# four-step-octaved_1_1.net
KiCad netlist of a schematic drawn in EAGLE
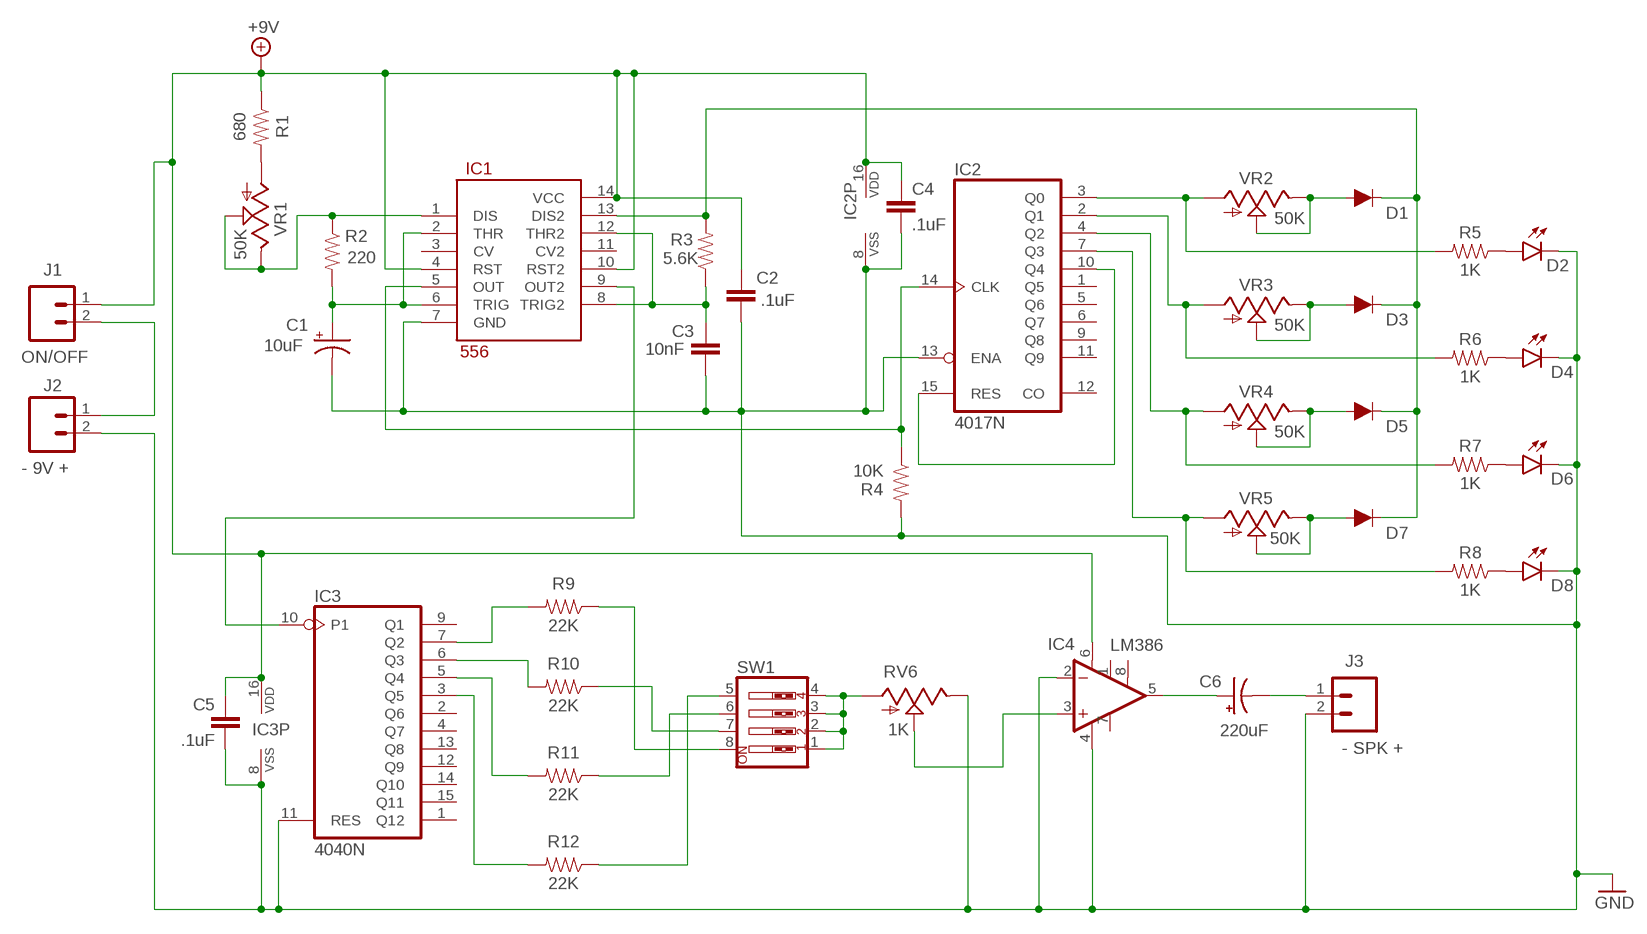
[diagram p0: schematic, sheet 1]

(export (version "E")
  (design (tool "Eeschema 10.0.6"))
  (components
    (comp (ref "C1")
      (value "10uF")
      (footprint "eagle-import:CPOL-RADIAL-2.5MM-5MM")
      (libsource (lib "eagle-import") (part "10UF-POLAR-RADIAL-2.5MM-25V-20%"))
    )
    (comp (ref "C2")
      (value ".1uF")
      (footprint "eagle-import:CAP-PTH-SMALL-KIT")
      (libsource (lib "eagle-import") (part "0.1UF-KIT-EZ-50V-20%"))
    )
    (comp (ref "C3")
      (value "10nF")
      (footprint "eagle-import:CAP-PTH-SMALL-KIT")
      (libsource (lib "eagle-import") (part "0.1UF-KIT-EZ-50V-20%"))
    )
    (comp (ref "C4")
      (value ".1uF")
      (footprint "eagle-import:CAP-PTH-SMALL-KIT")
      (libsource (lib "eagle-import") (part "0.1UF-KIT-EZ-50V-20%"))
    )
    (comp (ref "C5")
      (value ".1uF")
      (footprint "eagle-import:CAP-PTH-SMALL-KIT")
      (libsource (lib "eagle-import") (part "0.1UF-KIT-EZ-50V-20%"))
    )
    (comp (ref "C6")
      (value "220uF")
      (footprint "eagle-import:CPOL-RADIAL-2.5MM-5MM")
      (libsource (lib "eagle-import") (part "10UF-POLAR-RADIAL-2.5MM-25V-20%"))
    )
    (comp (ref "D1")
      (value "DIODE-PTH")
      (footprint "eagle-import:DIODE-1N4001")
      (libsource (lib "eagle-import") (part "DIODE-PTH"))
    )
    (comp (ref "D2")
      (value "LED3MM")
      (footprint "eagle-import:LED_3MM")
      (libsource (lib "eagle-import") (part "LED3MM"))
    )
    (comp (ref "D3")
      (value "DIODE-PTH")
      (footprint "eagle-import:DIODE-1N4001")
      (libsource (lib "eagle-import") (part "DIODE-PTH"))
    )
    (comp (ref "D4")
      (value "LED3MM")
      (footprint "eagle-import:LED_3MM")
      (libsource (lib "eagle-import") (part "LED3MM"))
    )
    (comp (ref "D5")
      (value "DIODE-PTH")
      (footprint "eagle-import:DIODE-1N4001")
      (libsource (lib "eagle-import") (part "DIODE-PTH"))
    )
    (comp (ref "D6")
      (value "LED3MM")
      (footprint "eagle-import:LED_3MM")
      (libsource (lib "eagle-import") (part "LED3MM"))
    )
    (comp (ref "D7")
      (value "DIODE-PTH")
      (footprint "eagle-import:DIODE-1N4001")
      (libsource (lib "eagle-import") (part "DIODE-PTH"))
    )
    (comp (ref "D8")
      (value "LED3MM")
      (footprint "eagle-import:LED_3MM")
      (libsource (lib "eagle-import") (part "LED3MM"))
    )
    (comp (ref "IC1")
      (value "556")
      (footprint "eagle-import:DIP14")
      (libsource (lib "eagle-import") (part "556"))
    )
    (comp (ref "IC2")
      (value "4017N")
      (footprint "eagle-import:DIL16")
      (libsource (lib "eagle-import") (part "4017N"))
    )
    (comp (ref "IC3")
      (value "4040N")
      (footprint "eagle-import:DIL16")
      (libsource (lib "eagle-import") (part "4040N"))
    )
    (comp (ref "IC4")
      (value "LM386")
      (footprint "eagle-import:DIP08")
      (libsource (lib "eagle-import") (part "LM386"))
    )
    (comp (ref "J1")
      (value "ON/OFF")
      (footprint "eagle-import:1X02")
      (libsource (lib "eagle-import") (part "CONN_02"))
    )
    (comp (ref "J2")
      (value "- 9V +")
      (footprint "eagle-import:1X02")
      (libsource (lib "eagle-import") (part "CONN_02"))
    )
    (comp (ref "J3")
      (value "- SPK +")
      (footprint "eagle-import:1X02")
      (libsource (lib "eagle-import") (part "CONN_02"))
    )
    (comp (ref "R1")
      (value "680")
      (footprint "eagle-import:AXIAL-0.3")
      (libsource (lib "eagle-import") (part "1KOHM-HORIZ-1/4W-1%"))
    )
    (comp (ref "R2")
      (value "220")
      (footprint "eagle-import:AXIAL-0.3")
      (libsource (lib "eagle-import") (part "1KOHM-HORIZ-1/4W-1%"))
    )
    (comp (ref "R3")
      (value "5.6K")
      (footprint "eagle-import:AXIAL-0.3")
      (libsource (lib "eagle-import") (part "1KOHM-HORIZ-1/4W-1%"))
    )
    (comp (ref "R4")
      (value "10K")
      (footprint "eagle-import:AXIAL-0.3")
      (libsource (lib "eagle-import") (part "1KOHM-HORIZ-1/4W-1%"))
    )
    (comp (ref "R5")
      (value "1K")
      (footprint "eagle-import:AXIAL-0.3")
      (libsource (lib "eagle-import") (part "1KOHM-HORIZ-1/4W-1%"))
    )
    (comp (ref "R6")
      (value "1K")
      (footprint "eagle-import:AXIAL-0.3")
      (libsource (lib "eagle-import") (part "1KOHM-HORIZ-1/4W-1%"))
    )
    (comp (ref "R7")
      (value "1K")
      (footprint "eagle-import:AXIAL-0.3")
      (libsource (lib "eagle-import") (part "1KOHM-HORIZ-1/4W-1%"))
    )
    (comp (ref "R8")
      (value "1K")
      (footprint "eagle-import:AXIAL-0.3")
      (libsource (lib "eagle-import") (part "1KOHM-HORIZ-1/4W-1%"))
    )
    (comp (ref "R9")
      (value "22K")
      (footprint "eagle-import:AXIAL-0.3")
      (libsource (lib "eagle-import") (part "1KOHM-HORIZ-1/4W-1%"))
    )
    (comp (ref "R10")
      (value "22K")
      (footprint "eagle-import:AXIAL-0.3")
      (libsource (lib "eagle-import") (part "1KOHM-HORIZ-1/4W-1%"))
    )
    (comp (ref "R11")
      (value "22K")
      (footprint "eagle-import:AXIAL-0.3")
      (libsource (lib "eagle-import") (part "1KOHM-HORIZ-1/4W-1%"))
    )
    (comp (ref "R12")
      (value "22K")
      (footprint "eagle-import:AXIAL-0.3")
      (libsource (lib "eagle-import") (part "1KOHM-HORIZ-1/4W-1%"))
    )
    (comp (ref "RV6")
      (value "1K")
      (footprint "eagle-import:TRIM_POT")
      (libsource (lib "eagle-import") (part "POTTRIM"))
    )
    (comp (ref "SW1")
      (value "SW_DIP-4")
      (footprint "eagle-import:EDG-04")
      (libsource (lib "eagle-import") (part "SW_DIP-4"))
    )
    (comp (ref "VR1")
      (value "50K")
      (footprint "eagle-import:TRIM_POT")
      (libsource (lib "eagle-import") (part "POTTRIM"))
    )
    (comp (ref "VR2")
      (value "50K")
      (footprint "eagle-import:TRIM_POT")
      (libsource (lib "eagle-import") (part "POTTRIM"))
    )
    (comp (ref "VR3")
      (value "50K")
      (footprint "eagle-import:TRIM_POT")
      (libsource (lib "eagle-import") (part "POTTRIM"))
    )
    (comp (ref "VR4")
      (value "50K")
      (footprint "eagle-import:TRIM_POT")
      (libsource (lib "eagle-import") (part "POTTRIM"))
    )
    (comp (ref "VR5")
      (value "50K")
      (footprint "eagle-import:TRIM_POT")
      (libsource (lib "eagle-import") (part "POTTRIM"))
    )
  )
  (nets
    (net (code "1") (name "+9V") (class "Default")
      (node (ref "C2") (pin "1") (pinfunction "1_1") (pintype "passive"))
      (node (ref "C4") (pin "1") (pinfunction "1_1") (pintype "passive"))
      (node (ref "C5") (pin "1") (pinfunction "1_1") (pintype "passive"))
      (node (ref "IC1") (pin "10") (pinfunction "RST2_10") (pintype "bidirectional"))
      (node (ref "IC1") (pin "14") (pinfunction "VCC_14") (pintype "bidirectional"))
      (node (ref "IC1") (pin "4") (pinfunction "RST_4") (pintype "bidirectional"))
      (node (ref "IC2") (pin "16") (pinfunction "VDD_16") (pintype "power_in"))
      (node (ref "IC3") (pin "16") (pinfunction "VDD_16") (pintype "power_in"))
      (node (ref "IC4") (pin "6") (pinfunction "V+_6") (pintype "power_in"))
      (node (ref "J1") (pin "1") (pinfunction "1_1") (pintype "passive"))
      (node (ref "R1") (pin "P$1") (pinfunction "1_P$1") (pintype "passive"))
    )
    (net (code "2") (name "GND") (class "Default")
      (node (ref "C1") (pin "2") (pinfunction "-_2") (pintype "passive"))
      (node (ref "C2") (pin "2") (pinfunction "2_2") (pintype "passive"))
      (node (ref "C3") (pin "2") (pinfunction "2_2") (pintype "passive"))
      (node (ref "C4") (pin "2") (pinfunction "2_2") (pintype "passive"))
      (node (ref "C5") (pin "2") (pinfunction "2_2") (pintype "passive"))
      (node (ref "D2") (pin "K") (pinfunction "C_K") (pintype "passive"))
      (node (ref "D4") (pin "K") (pinfunction "C_K") (pintype "passive"))
      (node (ref "D6") (pin "K") (pinfunction "C_K") (pintype "passive"))
      (node (ref "D8") (pin "K") (pinfunction "C_K") (pintype "passive"))
      (node (ref "IC1") (pin "7") (pinfunction "GND_7") (pintype "bidirectional"))
      (node (ref "IC2") (pin "13") (pinfunction "ENA_13") (pintype "input"))
      (node (ref "IC2") (pin "8") (pinfunction "VSS_8") (pintype "power_in"))
      (node (ref "IC3") (pin "11") (pinfunction "RES_11") (pintype "input"))
      (node (ref "IC3") (pin "8") (pinfunction "VSS_8") (pintype "power_in"))
      (node (ref "IC4") (pin "2") (pinfunction "-IN_2") (pintype "input"))
      (node (ref "IC4") (pin "4") (pinfunction "V-_4") (pintype "power_in"))
      (node (ref "J2") (pin "2") (pinfunction "2_2") (pintype "passive"))
      (node (ref "J3") (pin "2") (pinfunction "2_2") (pintype "passive"))
      (node (ref "R4") (pin "P$2") (pinfunction "2_P$2") (pintype "passive"))
      (node (ref "RV6") (pin "2") (pinfunction "E_2") (pintype "passive"))
    )
    (net (code "3") (name "Net-(C1-+)") (class "Default")
      (node (ref "C1") (pin "1") (pinfunction "+_1") (pintype "passive"))
      (node (ref "IC1") (pin "2") (pinfunction "THR_2") (pintype "bidirectional"))
      (node (ref "IC1") (pin "6") (pinfunction "TRIG_6") (pintype "bidirectional"))
      (node (ref "R2") (pin "P$2") (pinfunction "2_P$2") (pintype "passive"))
    )
    (net (code "4") (name "Net-(C6-+)") (class "Default")
      (node (ref "C6") (pin "1") (pinfunction "+_1") (pintype "passive"))
      (node (ref "IC4") (pin "5") (pinfunction "OUT_5") (pintype "output"))
    )
    (net (code "5") (name "Net-(C6--)") (class "Default")
      (node (ref "C6") (pin "2") (pinfunction "-_2") (pintype "passive"))
      (node (ref "J3") (pin "1") (pinfunction "1_1") (pintype "passive"))
    )
    (net (code "6") (name "Net-(IC1-DIS)") (class "Default")
      (node (ref "IC1") (pin "1") (pinfunction "DIS_1") (pintype "bidirectional"))
      (node (ref "R2") (pin "P$1") (pinfunction "1_P$1") (pintype "passive"))
      (node (ref "VR1") (pin "1") (pinfunction "S_1") (pintype "passive"))
      (node (ref "VR1") (pin "2") (pinfunction "E_2") (pintype "passive"))
    )
    (net (code "7") (name "Net-(IC1-DIS2)") (class "Default")
      (node (ref "D1") (pin "C") (pinfunction "C_C") (pintype "passive"))
      (node (ref "D3") (pin "C") (pinfunction "C_C") (pintype "passive"))
      (node (ref "D5") (pin "C") (pinfunction "C_C") (pintype "passive"))
      (node (ref "D7") (pin "C") (pinfunction "C_C") (pintype "passive"))
      (node (ref "IC1") (pin "13") (pinfunction "DIS2_13") (pintype "bidirectional"))
      (node (ref "R3") (pin "P$2") (pinfunction "2_P$2") (pintype "passive"))
    )
    (net (code "8") (name "Net-(IC1-OUT)") (class "Default")
      (node (ref "IC1") (pin "5") (pinfunction "OUT_5") (pintype "bidirectional"))
      (node (ref "IC2") (pin "14") (pinfunction "CLK_14") (pintype "input"))
      (node (ref "R4") (pin "P$1") (pinfunction "1_P$1") (pintype "passive"))
    )
    (net (code "9") (name "Net-(IC1-OUT2)") (class "Default")
      (node (ref "IC1") (pin "9") (pinfunction "OUT2_9") (pintype "bidirectional"))
      (node (ref "IC3") (pin "10") (pinfunction "P1_10") (pintype "input"))
    )
    (net (code "10") (name "Net-(IC1-THR2)") (class "Default")
      (node (ref "C3") (pin "1") (pinfunction "1_1") (pintype "passive"))
      (node (ref "IC1") (pin "12") (pinfunction "THR2_12") (pintype "bidirectional"))
      (node (ref "IC1") (pin "8") (pinfunction "TRIG2_8") (pintype "bidirectional"))
      (node (ref "R3") (pin "P$1") (pinfunction "1_P$1") (pintype "passive"))
    )
    (net (code "11") (name "Net-(IC2A-Q0)") (class "Default")
      (node (ref "IC2") (pin "3") (pinfunction "Q0_3") (pintype "output"))
      (node (ref "R5") (pin "P$2") (pinfunction "2_P$2") (pintype "passive"))
      (node (ref "VR2") (pin "3") (pinfunction "A_3") (pintype "passive"))
    )
    (net (code "12") (name "Net-(IC2A-Q1)") (class "Default")
      (node (ref "IC2") (pin "2") (pinfunction "Q1_2") (pintype "output"))
      (node (ref "R6") (pin "P$2") (pinfunction "2_P$2") (pintype "passive"))
      (node (ref "VR3") (pin "3") (pinfunction "A_3") (pintype "passive"))
    )
    (net (code "13") (name "Net-(IC2A-Q2)") (class "Default")
      (node (ref "IC2") (pin "4") (pinfunction "Q2_4") (pintype "output"))
      (node (ref "R7") (pin "P$2") (pinfunction "2_P$2") (pintype "passive"))
      (node (ref "VR4") (pin "3") (pinfunction "A_3") (pintype "passive"))
    )
    (net (code "14") (name "Net-(IC2A-Q3)") (class "Default")
      (node (ref "IC2") (pin "7") (pinfunction "Q3_7") (pintype "output"))
      (node (ref "R8") (pin "P$2") (pinfunction "2_P$2") (pintype "passive"))
      (node (ref "VR5") (pin "3") (pinfunction "A_3") (pintype "passive"))
    )
    (net (code "15") (name "Net-(IC2A-Q4)") (class "Default")
      (node (ref "IC2") (pin "10") (pinfunction "Q4_10") (pintype "output"))
      (node (ref "IC2") (pin "15") (pinfunction "RES_15") (pintype "input"))
    )
    (net (code "16") (name "Net-(IC3A-Q2)") (class "Default")
      (node (ref "IC3") (pin "7") (pinfunction "Q2_7") (pintype "output"))
      (node (ref "R9") (pin "P$2") (pinfunction "2_P$2") (pintype "passive"))
    )
    (net (code "17") (name "Net-(IC3A-Q3)") (class "Default")
      (node (ref "IC3") (pin "6") (pinfunction "Q3_6") (pintype "output"))
      (node (ref "R10") (pin "P$2") (pinfunction "2_P$2") (pintype "passive"))
    )
    (net (code "18") (name "Net-(IC3A-Q4)") (class "Default")
      (node (ref "IC3") (pin "5") (pinfunction "Q4_5") (pintype "output"))
      (node (ref "R11") (pin "P$2") (pinfunction "2_P$2") (pintype "passive"))
    )
    (net (code "19") (name "Net-(IC3A-Q5)") (class "Default")
      (node (ref "IC3") (pin "3") (pinfunction "Q5_3") (pintype "output"))
      (node (ref "R12") (pin "P$2") (pinfunction "2_P$2") (pintype "passive"))
    )
    (net (code "20") (name "Net-(IC4-+IN)") (class "Default")
      (node (ref "IC4") (pin "3") (pinfunction "+IN_3") (pintype "input"))
      (node (ref "RV6") (pin "1") (pinfunction "S_1") (pintype "passive"))
    )
    (net (code "21") (name "Net-(J1-Pad2)") (class "Default")
      (node (ref "J1") (pin "2") (pinfunction "2_2") (pintype "passive"))
      (node (ref "J2") (pin "1") (pinfunction "1_1") (pintype "passive"))
    )
    (net (code "22") (name "Net-(R1-2)") (class "Default")
      (node (ref "R1") (pin "P$2") (pinfunction "2_P$2") (pintype "passive"))
      (node (ref "VR1") (pin "3") (pinfunction "A_3") (pintype "passive"))
    )
    (net (code "23") (name "Net-(R5-1)") (class "Default")
      (node (ref "D2") (pin "A") (pinfunction "A_A") (pintype "passive"))
      (node (ref "R5") (pin "P$1") (pinfunction "1_P$1") (pintype "passive"))
    )
    (net (code "24") (name "Net-(R6-1)") (class "Default")
      (node (ref "D4") (pin "A") (pinfunction "A_A") (pintype "passive"))
      (node (ref "R6") (pin "P$1") (pinfunction "1_P$1") (pintype "passive"))
    )
    (net (code "25") (name "Net-(R7-1)") (class "Default")
      (node (ref "D6") (pin "A") (pinfunction "A_A") (pintype "passive"))
      (node (ref "R7") (pin "P$1") (pinfunction "1_P$1") (pintype "passive"))
    )
    (net (code "26") (name "Net-(R8-1)") (class "Default")
      (node (ref "D8") (pin "A") (pinfunction "A_A") (pintype "passive"))
      (node (ref "R8") (pin "P$1") (pinfunction "1_P$1") (pintype "passive"))
    )
    (net (code "27") (name "Net-(R9-1)") (class "Default")
      (node (ref "R9") (pin "P$1") (pinfunction "1_P$1") (pintype "passive"))
      (node (ref "SW1") (pin "8") (pinfunction "8_8") (pintype "passive"))
    )
    (net (code "28") (name "Net-(R10-1)") (class "Default")
      (node (ref "R10") (pin "P$1") (pinfunction "1_P$1") (pintype "passive"))
      (node (ref "SW1") (pin "7") (pinfunction "7_7") (pintype "passive"))
    )
    (net (code "29") (name "Net-(R11-1)") (class "Default")
      (node (ref "R11") (pin "P$1") (pinfunction "1_P$1") (pintype "passive"))
      (node (ref "SW1") (pin "6") (pinfunction "6_6") (pintype "passive"))
    )
    (net (code "30") (name "Net-(R12-1)") (class "Default")
      (node (ref "R12") (pin "P$1") (pinfunction "1_P$1") (pintype "passive"))
      (node (ref "SW1") (pin "5") (pinfunction "5_5") (pintype "passive"))
    )
    (net (code "31") (name "Net-(RV6-A)") (class "Default")
      (node (ref "RV6") (pin "3") (pinfunction "A_3") (pintype "passive"))
      (node (ref "SW1") (pin "1") (pinfunction "1_1") (pintype "passive"))
      (node (ref "SW1") (pin "2") (pinfunction "2_2") (pintype "passive"))
      (node (ref "SW1") (pin "3") (pinfunction "3_3") (pintype "passive"))
      (node (ref "SW1") (pin "4") (pinfunction "4_4") (pintype "passive"))
    )
    (net (code "32") (name "Net-(VR2-E)") (class "Default")
      (node (ref "D1") (pin "A") (pinfunction "A_A") (pintype "passive"))
      (node (ref "VR2") (pin "1") (pinfunction "S_1") (pintype "passive"))
      (node (ref "VR2") (pin "2") (pinfunction "E_2") (pintype "passive"))
    )
    (net (code "33") (name "Net-(VR3-E)") (class "Default")
      (node (ref "D3") (pin "A") (pinfunction "A_A") (pintype "passive"))
      (node (ref "VR3") (pin "1") (pinfunction "S_1") (pintype "passive"))
      (node (ref "VR3") (pin "2") (pinfunction "E_2") (pintype "passive"))
    )
    (net (code "34") (name "Net-(VR4-E)") (class "Default")
      (node (ref "D5") (pin "A") (pinfunction "A_A") (pintype "passive"))
      (node (ref "VR4") (pin "1") (pinfunction "S_1") (pintype "passive"))
      (node (ref "VR4") (pin "2") (pinfunction "E_2") (pintype "passive"))
    )
    (net (code "35") (name "Net-(VR5-E)") (class "Default")
      (node (ref "D7") (pin "A") (pinfunction "A_A") (pintype "passive"))
      (node (ref "VR5") (pin "1") (pinfunction "S_1") (pintype "passive"))
      (node (ref "VR5") (pin "2") (pinfunction "E_2") (pintype "passive"))
    )
    (net (code "36") (name "unconnected-(IC1-CV-Pad3)") (class "Default")
      (node (ref "IC1") (pin "3") (pinfunction "CV_3") (pintype "bidirectional"))
    )
    (net (code "37") (name "unconnected-(IC1-CV2-Pad11)") (class "Default")
      (node (ref "IC1") (pin "11") (pinfunction "CV2_11") (pintype "bidirectional"))
    )
    (net (code "38") (name "unconnected-(IC2A-CO-Pad12)") (class "Default")
      (node (ref "IC2") (pin "12") (pinfunction "CO_12") (pintype "output"))
    )
    (net (code "39") (name "unconnected-(IC2A-Q5-Pad1)") (class "Default")
      (node (ref "IC2") (pin "1") (pinfunction "Q5_1") (pintype "output"))
    )
    (net (code "40") (name "unconnected-(IC2A-Q6-Pad5)") (class "Default")
      (node (ref "IC2") (pin "5") (pinfunction "Q6_5") (pintype "output"))
    )
    (net (code "41") (name "unconnected-(IC2A-Q7-Pad6)") (class "Default")
      (node (ref "IC2") (pin "6") (pinfunction "Q7_6") (pintype "output"))
    )
    (net (code "42") (name "unconnected-(IC2A-Q8-Pad9)") (class "Default")
      (node (ref "IC2") (pin "9") (pinfunction "Q8_9") (pintype "output"))
    )
    (net (code "43") (name "unconnected-(IC2A-Q9-Pad11)") (class "Default")
      (node (ref "IC2") (pin "11") (pinfunction "Q9_11") (pintype "output"))
    )
    (net (code "44") (name "unconnected-(IC3A-Q1-Pad9)") (class "Default")
      (node (ref "IC3") (pin "9") (pinfunction "Q1_9") (pintype "output"))
    )
    (net (code "45") (name "unconnected-(IC3A-Q6-Pad2)") (class "Default")
      (node (ref "IC3") (pin "2") (pinfunction "Q6_2") (pintype "output"))
    )
    (net (code "46") (name "unconnected-(IC3A-Q7-Pad4)") (class "Default")
      (node (ref "IC3") (pin "4") (pinfunction "Q7_4") (pintype "output"))
    )
    (net (code "47") (name "unconnected-(IC3A-Q8-Pad13)") (class "Default")
      (node (ref "IC3") (pin "13") (pinfunction "Q8_13") (pintype "output"))
    )
    (net (code "48") (name "unconnected-(IC3A-Q9-Pad12)") (class "Default")
      (node (ref "IC3") (pin "12") (pinfunction "Q9_12") (pintype "output"))
    )
    (net (code "49") (name "unconnected-(IC3A-Q10-Pad14)") (class "Default")
      (node (ref "IC3") (pin "14") (pinfunction "Q10_14") (pintype "output"))
    )
    (net (code "50") (name "unconnected-(IC3A-Q11-Pad15)") (class "Default")
      (node (ref "IC3") (pin "15") (pinfunction "Q11_15") (pintype "output"))
    )
    (net (code "51") (name "unconnected-(IC3A-Q12-Pad1)") (class "Default")
      (node (ref "IC3") (pin "1") (pinfunction "Q12_1") (pintype "output"))
    )
    (net (code "52") (name "unconnected-(IC4-BP-Pad7)") (class "Default")
      (node (ref "IC4") (pin "7") (pinfunction "BP_7") (pintype "bidirectional"))
    )
    (net (code "53") (name "unconnected-(IC4-GAIN-Pad1)") (class "Default")
      (node (ref "IC4") (pin "1") (pinfunction "GAIN_1") (pintype "bidirectional"))
    )
    (net (code "54") (name "unconnected-(IC4-GAIN-Pad8)") (class "Default")
      (node (ref "IC4") (pin "8") (pinfunction "GAIN_8") (pintype "bidirectional"))
    )
  )
)
